# CH32V467WEU-R0.net
KiCad netlist of a schematic drawn in Altium Designer
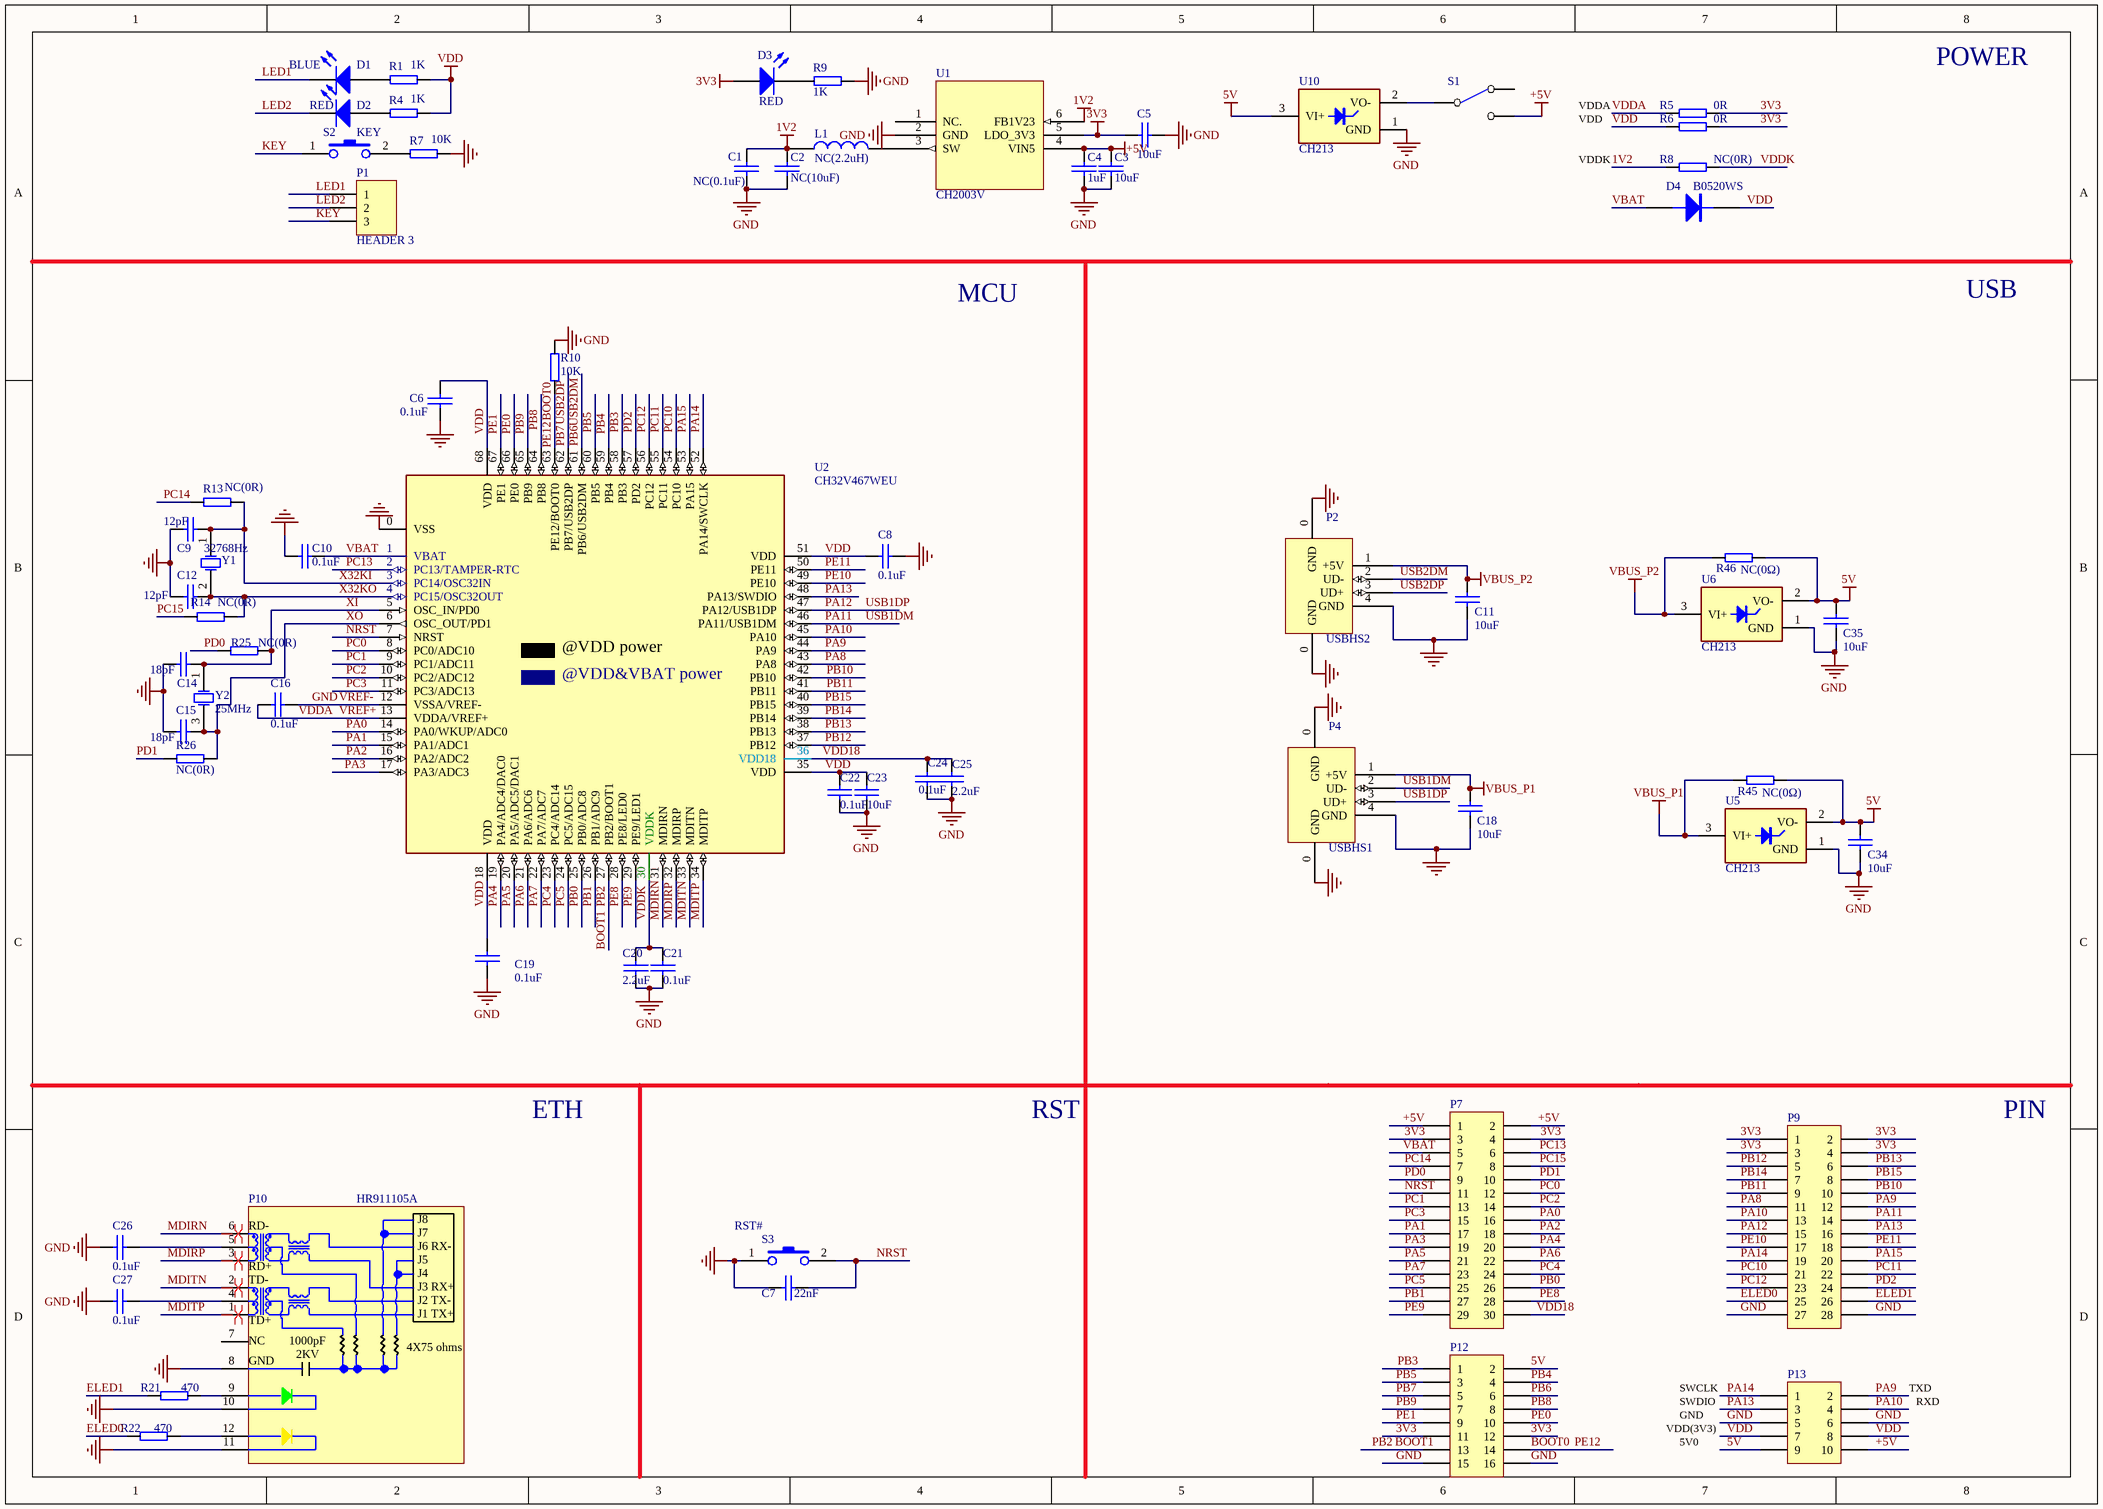
[diagram p0: CH32V467WEU-R0.SchDoc]

(export (version "E")
  (design (tool "Eeschema 10.0.6"))
  (components
    (comp (ref "C1")
      (value "NC(0.1uF)")
      (footprint "0402_C")
      (description "Capacitor")
      (libsource (lib "") (part "CAP_2"))
    )
    (comp (ref "C2")
      (value "NC(10uF)")
      (footprint "0603_C")
      (description "Capacitor")
      (libsource (lib "") (part "CAP_1"))
    )
    (comp (ref "C3")
      (value "10uF")
      (footprint "0603_C")
      (description "Capacitor")
      (libsource (lib "") (part "CAP_1"))
    )
    (comp (ref "C4")
      (value "1uF")
      (footprint "0402_C")
      (description "Capacitor")
      (libsource (lib "") (part "CAP_2"))
    )
    (comp (ref "C5")
      (value "10uF")
      (footprint "0603_C")
      (description "Capacitor")
      (libsource (lib "") (part "CAP_1"))
    )
    (comp (ref "C6")
      (value "0.1uF")
      (footprint "0402_C")
      (description "Capacitor")
      (libsource (lib "") (part "CAP_1"))
    )
    (comp (ref "C7")
      (value "22nF")
      (footprint "0402_C")
      (description "Capacitor")
      (libsource (lib "*") (part "CAP"))
    )
    (comp (ref "C8")
      (value "0.1uF")
      (footprint "0402_C")
      (description "Capacitor")
      (libsource (lib "") (part "CAP_1"))
    )
    (comp (ref "C9")
      (value "12pF")
      (footprint "0402_C")
      (description "Capacitor")
      (libsource (lib "") (part "CAP_1"))
    )
    (comp (ref "C10")
      (value "0.1uF")
      (footprint "0402_C")
      (description "Capacitor")
      (libsource (lib "") (part "CAP_1"))
    )
    (comp (ref "C11")
      (value "10uF")
      (footprint "0603_C")
      (description "Capacitor")
      (libsource (lib "*") (part "CAP"))
    )
    (comp (ref "C12")
      (value "12pF")
      (footprint "0402_C")
      (description "Capacitor")
      (libsource (lib "") (part "CAP_1"))
    )
    (comp (ref "C14")
      (value "18pF")
      (footprint "0402_C")
      (description "Capacitor")
      (libsource (lib "") (part "CAP_1"))
    )
    (comp (ref "C15")
      (value "18pF")
      (footprint "0402_C")
      (description "Capacitor")
      (libsource (lib "") (part "CAP_1"))
    )
    (comp (ref "C16")
      (value "0.1uF")
      (footprint "0402_C")
      (description "Capacitor")
      (libsource (lib "") (part "CAP_1"))
    )
    (comp (ref "C18")
      (value "10uF")
      (footprint "0603_C")
      (description "Capacitor")
      (libsource (lib "*") (part "CAP"))
    )
    (comp (ref "C19")
      (value "0.1uF")
      (footprint "0402_C")
      (description "Capacitor")
      (libsource (lib "") (part "CAP_1"))
    )
    (comp (ref "C20")
      (value "2.2uF")
      (footprint "0402_C")
      (description "Capacitor")
      (libsource (lib "") (part "CAP_1"))
    )
    (comp (ref "C21")
      (value "0.1uF")
      (footprint "0402_C")
      (description "Capacitor")
      (libsource (lib "") (part "CAP_1"))
    )
    (comp (ref "C22")
      (value "0.1uF")
      (footprint "0402_C")
      (description "Capacitor")
      (libsource (lib "") (part "CAP_1"))
    )
    (comp (ref "C23")
      (value "10uF")
      (footprint "0603_C")
      (description "Capacitor")
      (libsource (lib "") (part "CAP_1"))
    )
    (comp (ref "C24")
      (value "0.1uF")
      (footprint "0402_C")
      (description "Capacitor")
      (libsource (lib "") (part "CAP_1"))
    )
    (comp (ref "C25")
      (value "2.2uF")
      (footprint "0402_C")
      (description "Capacitor")
      (libsource (lib "") (part "CAP_1"))
    )
    (comp (ref "C26")
      (value "0.1uF")
      (footprint "0402_C")
      (description "Capacitor")
      (libsource (lib "wch_sch_others") (part "CAP"))
    )
    (comp (ref "C27")
      (value "0.1uF")
      (footprint "0402_C")
      (description "Capacitor")
      (libsource (lib "wch_sch_others") (part "CAP"))
    )
    (comp (ref "C34")
      (value "10uF")
      (footprint "0603_C")
      (description "Capacitor")
      (libsource (lib "*") (part "CAP"))
    )
    (comp (ref "C35")
      (value "10uF")
      (footprint "0603_C")
      (description "Capacitor")
      (libsource (lib "*") (part "CAP"))
    )
    (comp (ref "D1")
      (value "BLUE")
      (footprint "0603+")
      (description "Typical INFRARED GaAs LED")
      (fields (field (name "PUBLISHER") "Altium Limited"))
      (libsource (lib "*") (part "LED0"))
    )
    (comp (ref "D2")
      (value "RED")
      (footprint "0603+")
      (description "Typical INFRARED GaAs LED")
      (fields (field (name "PUBLISHER") "Altium Limited"))
      (libsource (lib "*") (part "LED0"))
    )
    (comp (ref "D3")
      (value "RED")
      (footprint "0603+")
      (description "Typical INFRARED GaAs LED")
      (fields (field (name "PUBLISHER") "Altium Limited"))
      (libsource (lib "*") (part "LED0"))
    )
    (comp (ref "D4")
      (value "B0520WS")
      (footprint "SOD-323")
      (description "Diode")
      (libsource (lib "*") (part "DIODE"))
    )
    (comp (ref "L1") (value "NC(2.2uH)") (footprint "CD32") (libsource (lib "*") (part "INDUCTOR")))
    (comp (ref "P1")
      (value "HEADER 3")
      (footprint "SIP3-2.54MM")
      (description "Header, 3-Pin")
      (libsource (lib "wch_sch_others") (part "HEADER 3"))
    )
    (comp (ref "P2")
      (value "USBHS2")
      (footprint "USBAF")
      (description "USB Port")
      (libsource (lib "*") (part "USB"))
    )
    (comp (ref "P4")
      (value "USBHS1")
      (footprint "USBAF")
      (description "USB Port")
      (libsource (lib "*") (part "USB"))
    )
    (comp (ref "P7")
      (value "HEADER 15x2")
      (footprint "MYPCB:IDC30-2.54MM")
      (description "Header, 15-Pin, Dual row")
      (libsource (lib "wch_sch_others") (part "HEADER 15x2"))
    )
    (comp (ref "P9")
      (value "HEADER 14x2")
      (footprint "MYPCB:IDC28-2.54MM")
      (description "Header, 14-Pin, Dual row")
      (libsource (lib "wch_sch_others") (part "HEADER 14x2"))
    )
    (comp (ref "P10") (value "HR911105A") (footprint "HR911105A") (libsource (lib "*") (part "HR911105A")))
    (comp (ref "P12")
      (value "Ppin")
      (footprint "IDC16-2.54mm")
      (description "Header, 8-Pin, Dual row, Right Angle")
      (fields (field (name "PUBLISHER") "Altium Limited"))
      (libsource (lib "Miscellaneous Connectors") (part "Header 8X2H"))
    )
    (comp (ref "P13")
      (value "LINK")
      (footprint "IDC10-2.54mm")
      (description "Header, 5-Pin, Dual row, Right Angle")
      (fields (field (name "PUBLISHER") "Altium Limited"))
      (libsource (lib "Miscellaneous Connectors") (part "Header 5X2H"))
    )
    (comp (ref "R1") (value "1K") (footprint "0402") (libsource (lib "wch_sch_others") (part "RES")))
    (comp (ref "R4") (value "1K") (footprint "0402") (libsource (lib "wch_sch_others") (part "RES")))
    (comp (ref "R5") (value "0R") (footprint "0402") (libsource (lib "*") (part "R")))
    (comp (ref "R6") (value "0R") (footprint "0402") (libsource (lib "*") (part "R")))
    (comp (ref "R7") (value "10K") (footprint "0402") (libsource (lib "wch_sch_others") (part "RES")))
    (comp (ref "R8") (value "NC(0R)") (footprint "0402") (libsource (lib "*") (part "R")))
    (comp (ref "R9") (value "1K") (footprint "0402") (libsource (lib "wch_sch_others") (part "RES")))
    (comp (ref "R10") (value "10K") (footprint "0402") (libsource (lib "wch_sch_others") (part "RES")))
    (comp (ref "R13") (value "NC(0R)") (footprint "0402") (libsource (lib "wch_sch_others") (part "RES")))
    (comp (ref "R14") (value "NC(0R)") (footprint "0402") (libsource (lib "wch_sch_others") (part "RES")))
    (comp (ref "R21") (value "470") (footprint "0402") (libsource (lib "wch_sch_others") (part "RES")))
    (comp (ref "R22") (value "470") (footprint "0402") (libsource (lib "wch_sch_others") (part "RES")))
    (comp (ref "R25") (value "NC(0R)") (footprint "0402") (libsource (lib "wch_sch_others") (part "RES")))
    (comp (ref "R26") (value "NC(0R)") (footprint "0402") (libsource (lib "wch_sch_others") (part "RES")))
    (comp (ref "R45") (value "NC(0Ω)") (footprint "0402") (libsource (lib "wch_sch_others") (part "RES")))
    (comp (ref "R46") (value "NC(0Ω)") (footprint "0402") (libsource (lib "wch_sch_others") (part "RES")))
    (comp (ref "S1") (value "SW SPDT") (footprint "SW1") (libsource (lib "*") (part "SW SPDT")))
    (comp (ref "S2")
      (value "KEY")
      (footprint "SMD_6.1x3.65x2.5mm-KEY")
      (libsource (lib "wch_sch_others") (part "KEY1"))
    )
    (comp (ref "S3")
      (value "RST#")
      (footprint "SMD_6.1x3.65x2.5mm-KEY")
      (libsource (lib "wch_sch_others") (part "KEY1"))
    )
    (comp (ref "U1")
      (value "CH2003V")
      (footprint "SOT-23-6")
      (description "Step-Down DC-DC Converter, 5V input, 1.23V * 800mA output, with LDO 3.3V * 200mA")
      (libsource (lib "CHXXX") (part "CH2003V"))
    )
    (comp (ref "U2")
      (value "CH32V467WEU")
      (footprint "QFN68_8X8")
      (description "RISC-V FPU HD-MCU, 175MHz, USB_480M, 100M Ethernet & Phy, CAN, ADC, DAC, SRAM")
      (libsource (lib "CHXXX") (part "CH32V467WEU"))
    )
    (comp (ref "U5")
      (value "CH213")
      (footprint "SOT-23-3")
      (description "Ideal Diode 5V*1A")
      (libsource (lib "CHXXX") (part "CH213E"))
    )
    (comp (ref "U6")
      (value "CH213")
      (footprint "SOT-23-3")
      (description "Ideal Diode 5V*1A")
      (libsource (lib "CHXXX") (part "CH213E"))
    )
    (comp (ref "U10")
      (value "CH213")
      (footprint "SOT-23-3")
      (description "Ideal Diode 5V*1A")
      (libsource (lib "CHXXX") (part "CH213E"))
    )
    (comp (ref "Y1")
      (value "32768Hz")
      (footprint "FC-135")
      (description "Crystal Oscillator")
      (fields (field (name "PUBLISHER") "Altium Limited"))
      (libsource (lib "*") (part "XTAL"))
    )
    (comp (ref "Y2")
      (value "25MHz")
      (footprint "XT3225")
      (description "Crystal Oscillator")
      (fields (field (name "PUBLISHER") "Altium Limited"))
      (libsource (lib "") (part "XTAL_1"))
    )
  )
  (nets
    (net (code "1") (name "+5V") (class "Default")
      (node (ref "C3") (pin "2") (pinfunction "2_2") (pintype "passive"))
      (node (ref "C4") (pin "2") (pinfunction "2_2") (pintype "passive"))
      (node (ref "P13") (pin "10") (pinfunction "10_10") (pintype "passive"))
      (node (ref "P7") (pin "1") (pinfunction "1_1") (pintype "passive"))
      (node (ref "P7") (pin "2") (pinfunction "2_2") (pintype "passive"))
      (node (ref "S1") (pin "2") (pinfunction "NC_2") (pintype "passive"))
      (node (ref "U1") (pin "4") (pinfunction "VIN5_4") (pintype "power_in"))
    )
    (net (code "3") (name "/BOOT0") (class "Default")
      (node (ref "P12") (pin "14") (pinfunction "14_14") (pintype "passive"))
      (node (ref "R10") (pin "2") (pintype "passive"))
      (node (ref "U2") (pin "63") (pinfunction "PE12/BOOT0_63") (pintype "bidirectional"))
    )
    (net (code "4") (name "/BOOT1") (class "Default")
      (node (ref "P12") (pin "13") (pinfunction "13_13") (pintype "passive"))
      (node (ref "U2") (pin "27") (pinfunction "PB2/BOOT1_27") (pintype "bidirectional"))
    )
    (net (code "5") (name "/ELED0") (class "Default")
      (node (ref "P9") (pin "25") (pinfunction "25_25") (pintype "passive"))
      (node (ref "R22") (pin "1") (pintype "passive"))
    )
    (net (code "6") (name "/ELED1") (class "Default")
      (node (ref "P9") (pin "26") (pinfunction "26_26") (pintype "passive"))
      (node (ref "R21") (pin "1") (pintype "passive"))
    )
    (net (code "7") (name "/KEY") (class "Default")
      (node (ref "P1") (pin "3") (pinfunction "3_3") (pintype "passive"))
      (node (ref "S2") (pin "1") (pinfunction "1_1") (pintype "passive"))
    )
    (net (code "8") (name "/LED1") (class "Default")
      (node (ref "D1") (pin "2") (pinfunction "K_2") (pintype "passive"))
      (node (ref "P1") (pin "1") (pinfunction "1_1") (pintype "passive"))
    )
    (net (code "9") (name "/LED2") (class "Default")
      (node (ref "D2") (pin "2") (pinfunction "K_2") (pintype "passive"))
      (node (ref "P1") (pin "2") (pinfunction "2_2") (pintype "passive"))
    )
    (net (code "10") (name "/MDIRN") (class "Default")
      (node (ref "P10") (pin "6") (pintype "passive"))
      (node (ref "U2") (pin "31") (pinfunction "MDIRN_31") (pintype "bidirectional"))
    )
    (net (code "11") (name "/MDIRP") (class "Default")
      (node (ref "P10") (pin "3") (pintype "passive"))
      (node (ref "U2") (pin "32") (pinfunction "MDIRP_32") (pintype "bidirectional"))
    )
    (net (code "12") (name "/MDITN") (class "Default")
      (node (ref "P10") (pin "2") (pintype "passive"))
      (node (ref "U2") (pin "33") (pinfunction "MDITN_33") (pintype "bidirectional"))
    )
    (net (code "13") (name "/MDITP") (class "Default")
      (node (ref "P10") (pin "1") (pintype "passive"))
      (node (ref "U2") (pin "34") (pinfunction "MDITP_34") (pintype "bidirectional"))
    )
    (net (code "14") (name "/NRST") (class "Default")
      (node (ref "C7") (pin "2") (pinfunction "2_2") (pintype "passive"))
      (node (ref "P7") (pin "11") (pinfunction "11_11") (pintype "passive"))
      (node (ref "S3") (pin "2") (pinfunction "2_2") (pintype "passive"))
      (node (ref "U2") (pin "7") (pinfunction "NRST_7") (pintype "input"))
    )
    (net (code "15") (name "/PA0") (class "Default")
      (node (ref "P7") (pin "16") (pinfunction "16_16") (pintype "passive"))
      (node (ref "U2") (pin "14") (pinfunction "PA0/WKUP/ADC0_14") (pintype "bidirectional"))
    )
    (net (code "16") (name "/PA1") (class "Default")
      (node (ref "P7") (pin "17") (pinfunction "17_17") (pintype "passive"))
      (node (ref "U2") (pin "15") (pinfunction "PA1/ADC1_15") (pintype "bidirectional"))
    )
    (net (code "17") (name "/PA2") (class "Default")
      (node (ref "P7") (pin "18") (pinfunction "18_18") (pintype "passive"))
      (node (ref "U2") (pin "16") (pinfunction "PA2/ADC2_16") (pintype "bidirectional"))
    )
    (net (code "18") (name "/PA3") (class "Default")
      (node (ref "P7") (pin "19") (pinfunction "19_19") (pintype "passive"))
      (node (ref "U2") (pin "17") (pinfunction "PA3/ADC3_17") (pintype "bidirectional"))
    )
    (net (code "19") (name "/PA4") (class "Default")
      (node (ref "P7") (pin "20") (pinfunction "20_20") (pintype "passive"))
      (node (ref "U2") (pin "19") (pinfunction "PA4/ADC4/DAC0_19") (pintype "bidirectional"))
    )
    (net (code "20") (name "/PA5") (class "Default")
      (node (ref "P7") (pin "21") (pinfunction "21_21") (pintype "passive"))
      (node (ref "U2") (pin "20") (pinfunction "PA5/ADC5/DAC1_20") (pintype "bidirectional"))
    )
    (net (code "21") (name "/PA6") (class "Default")
      (node (ref "P7") (pin "22") (pinfunction "22_22") (pintype "passive"))
      (node (ref "U2") (pin "21") (pinfunction "PA6/ADC6_21") (pintype "bidirectional"))
    )
    (net (code "22") (name "/PA7") (class "Default")
      (node (ref "P7") (pin "23") (pinfunction "23_23") (pintype "passive"))
      (node (ref "U2") (pin "22") (pinfunction "PA7/ADC7_22") (pintype "bidirectional"))
    )
    (net (code "23") (name "/PA8") (class "Default")
      (node (ref "P9") (pin "11") (pinfunction "11_11") (pintype "passive"))
      (node (ref "U2") (pin "43") (pinfunction "PA8_43") (pintype "bidirectional"))
    )
    (net (code "24") (name "/PA9") (class "Default")
      (node (ref "P13") (pin "2") (pinfunction "2_2") (pintype "passive"))
      (node (ref "P9") (pin "12") (pinfunction "12_12") (pintype "passive"))
      (node (ref "U2") (pin "44") (pinfunction "PA9_44") (pintype "bidirectional"))
    )
    (net (code "25") (name "/PA10") (class "Default")
      (node (ref "P13") (pin "4") (pinfunction "4_4") (pintype "passive"))
      (node (ref "P9") (pin "13") (pinfunction "13_13") (pintype "passive"))
      (node (ref "U2") (pin "45") (pinfunction "PA10_45") (pintype "bidirectional"))
    )
    (net (code "26") (name "/PA11") (class "Default")
      (node (ref "P4") (pin "2") (pinfunction "UD-_2") (pintype "bidirectional"))
      (node (ref "P9") (pin "14") (pinfunction "14_14") (pintype "passive"))
      (node (ref "U2") (pin "46") (pinfunction "PA11/USB1DM_46") (pintype "bidirectional"))
    )
    (net (code "27") (name "/PA12") (class "Default")
      (node (ref "P4") (pin "3") (pinfunction "UD+_3") (pintype "bidirectional"))
      (node (ref "P9") (pin "15") (pinfunction "15_15") (pintype "passive"))
      (node (ref "U2") (pin "47") (pinfunction "PA12/USB1DP_47") (pintype "bidirectional"))
    )
    (net (code "28") (name "/PA13") (class "Default")
      (node (ref "P13") (pin "3") (pinfunction "3_3") (pintype "passive"))
      (node (ref "P9") (pin "16") (pinfunction "16_16") (pintype "passive"))
      (node (ref "U2") (pin "48") (pinfunction "PA13/SWDIO_48") (pintype "bidirectional"))
    )
    (net (code "29") (name "/PA14") (class "Default")
      (node (ref "P13") (pin "1") (pinfunction "1_1") (pintype "passive"))
      (node (ref "P9") (pin "19") (pinfunction "19_19") (pintype "passive"))
      (node (ref "U2") (pin "52") (pinfunction "PA14/SWCLK_52") (pintype "bidirectional"))
    )
    (net (code "30") (name "/PA15") (class "Default")
      (node (ref "P9") (pin "20") (pinfunction "20_20") (pintype "passive"))
      (node (ref "U2") (pin "53") (pinfunction "PA15_53") (pintype "bidirectional"))
    )
    (net (code "31") (name "/PB0") (class "Default")
      (node (ref "P7") (pin "26") (pinfunction "26_26") (pintype "passive"))
      (node (ref "U2") (pin "25") (pinfunction "PB0/ADC8_25") (pintype "bidirectional"))
    )
    (net (code "32") (name "/PB1") (class "Default")
      (node (ref "P7") (pin "27") (pinfunction "27_27") (pintype "passive"))
      (node (ref "U2") (pin "26") (pinfunction "PB1/ADC9_26") (pintype "bidirectional"))
    )
    (net (code "33") (name "/PB3") (class "Default")
      (node (ref "P12") (pin "1") (pinfunction "1_1") (pintype "passive"))
      (node (ref "U2") (pin "58") (pinfunction "PB3_58") (pintype "bidirectional"))
    )
    (net (code "34") (name "/PB4") (class "Default")
      (node (ref "P12") (pin "4") (pinfunction "4_4") (pintype "passive"))
      (node (ref "U2") (pin "59") (pinfunction "PB4_59") (pintype "bidirectional"))
    )
    (net (code "35") (name "/PB5") (class "Default")
      (node (ref "P12") (pin "3") (pinfunction "3_3") (pintype "passive"))
      (node (ref "U2") (pin "60") (pinfunction "PB5_60") (pintype "bidirectional"))
    )
    (net (code "36") (name "/PB6") (class "Default")
      (node (ref "P12") (pin "6") (pinfunction "6_6") (pintype "passive"))
      (node (ref "P2") (pin "2") (pinfunction "UD-_2") (pintype "bidirectional"))
      (node (ref "U2") (pin "61") (pinfunction "PB6/USB2DM_61") (pintype "bidirectional"))
    )
    (net (code "37") (name "/PB7") (class "Default")
      (node (ref "P12") (pin "5") (pinfunction "5_5") (pintype "passive"))
      (node (ref "P2") (pin "3") (pinfunction "UD+_3") (pintype "bidirectional"))
      (node (ref "U2") (pin "62") (pinfunction "PB7/USB2DP_62") (pintype "bidirectional"))
    )
    (net (code "38") (name "/PB8") (class "Default")
      (node (ref "P12") (pin "8") (pinfunction "8_8") (pintype "passive"))
      (node (ref "U2") (pin "64") (pinfunction "PB8_64") (pintype "bidirectional"))
    )
    (net (code "39") (name "/PB9") (class "Default")
      (node (ref "P12") (pin "7") (pinfunction "7_7") (pintype "passive"))
      (node (ref "U2") (pin "65") (pinfunction "PB9_65") (pintype "bidirectional"))
    )
    (net (code "40") (name "/PB10") (class "Default")
      (node (ref "P9") (pin "10") (pinfunction "10_10") (pintype "passive"))
      (node (ref "U2") (pin "42") (pinfunction "PB10_42") (pintype "bidirectional"))
    )
    (net (code "41") (name "/PB11") (class "Default")
      (node (ref "P9") (pin "9") (pinfunction "9_9") (pintype "passive"))
      (node (ref "U2") (pin "41") (pinfunction "PB11_41") (pintype "bidirectional"))
    )
    (net (code "42") (name "/PB12") (class "Default")
      (node (ref "P9") (pin "5") (pinfunction "5_5") (pintype "passive"))
      (node (ref "U2") (pin "37") (pinfunction "PB12_37") (pintype "bidirectional"))
    )
    (net (code "43") (name "/PB13") (class "Default")
      (node (ref "P9") (pin "6") (pinfunction "6_6") (pintype "passive"))
      (node (ref "U2") (pin "38") (pinfunction "PB13_38") (pintype "bidirectional"))
    )
    (net (code "44") (name "/PB14") (class "Default")
      (node (ref "P9") (pin "7") (pinfunction "7_7") (pintype "passive"))
      (node (ref "U2") (pin "39") (pinfunction "PB14_39") (pintype "bidirectional"))
    )
    (net (code "45") (name "/PB15") (class "Default")
      (node (ref "P9") (pin "8") (pinfunction "8_8") (pintype "passive"))
      (node (ref "U2") (pin "40") (pinfunction "PB15_40") (pintype "bidirectional"))
    )
    (net (code "46") (name "/PC0") (class "Default")
      (node (ref "P7") (pin "12") (pinfunction "12_12") (pintype "passive"))
      (node (ref "U2") (pin "8") (pinfunction "PC0/ADC10_8") (pintype "bidirectional"))
    )
    (net (code "47") (name "/PC1") (class "Default")
      (node (ref "P7") (pin "13") (pinfunction "13_13") (pintype "passive"))
      (node (ref "U2") (pin "9") (pinfunction "PC1/ADC11_9") (pintype "bidirectional"))
    )
    (net (code "48") (name "/PC2") (class "Default")
      (node (ref "P7") (pin "14") (pinfunction "14_14") (pintype "passive"))
      (node (ref "U2") (pin "10") (pinfunction "PC2/ADC12_10") (pintype "bidirectional"))
    )
    (net (code "49") (name "/PC3") (class "Default")
      (node (ref "P7") (pin "15") (pinfunction "15_15") (pintype "passive"))
      (node (ref "U2") (pin "11") (pinfunction "PC3/ADC13_11") (pintype "bidirectional"))
    )
    (net (code "50") (name "/PC4") (class "Default")
      (node (ref "P7") (pin "24") (pinfunction "24_24") (pintype "passive"))
      (node (ref "U2") (pin "23") (pinfunction "PC4/ADC14_23") (pintype "bidirectional"))
    )
    (net (code "51") (name "/PC5") (class "Default")
      (node (ref "P7") (pin "25") (pinfunction "25_25") (pintype "passive"))
      (node (ref "U2") (pin "24") (pinfunction "PC5/ADC15_24") (pintype "bidirectional"))
    )
    (net (code "52") (name "/PC10") (class "Default")
      (node (ref "P9") (pin "21") (pinfunction "21_21") (pintype "passive"))
      (node (ref "U2") (pin "54") (pinfunction "PC10_54") (pintype "bidirectional"))
    )
    (net (code "53") (name "/PC11") (class "Default")
      (node (ref "P9") (pin "22") (pinfunction "22_22") (pintype "passive"))
      (node (ref "U2") (pin "55") (pinfunction "PC11_55") (pintype "bidirectional"))
    )
    (net (code "54") (name "/PC12") (class "Default")
      (node (ref "P9") (pin "23") (pinfunction "23_23") (pintype "passive"))
      (node (ref "U2") (pin "56") (pinfunction "PC12_56") (pintype "bidirectional"))
    )
    (net (code "55") (name "/PC13") (class "Default")
      (node (ref "P7") (pin "6") (pinfunction "6_6") (pintype "passive"))
      (node (ref "U2") (pin "2") (pinfunction "PC13/TAMPER-RTC_2") (pintype "bidirectional"))
    )
    (net (code "56") (name "/PC14") (class "Default")
      (node (ref "P7") (pin "7") (pinfunction "7_7") (pintype "passive"))
      (node (ref "R13") (pin "1") (pintype "passive"))
    )
    (net (code "57") (name "/PC15") (class "Default")
      (node (ref "P7") (pin "8") (pinfunction "8_8") (pintype "passive"))
      (node (ref "R14") (pin "1") (pintype "passive"))
    )
    (net (code "58") (name "/PD0") (class "Default")
      (node (ref "P7") (pin "9") (pinfunction "9_9") (pintype "passive"))
      (node (ref "R25") (pin "1") (pintype "passive"))
    )
    (net (code "59") (name "/PD1") (class "Default")
      (node (ref "P7") (pin "10") (pinfunction "10_10") (pintype "passive"))
      (node (ref "R26") (pin "2") (pintype "passive"))
    )
    (net (code "60") (name "/PD2") (class "Default")
      (node (ref "P9") (pin "24") (pinfunction "24_24") (pintype "passive"))
      (node (ref "U2") (pin "57") (pinfunction "PD2_57") (pintype "bidirectional"))
    )
    (net (code "61") (name "/PE0") (class "Default")
      (node (ref "P12") (pin "10") (pinfunction "10_10") (pintype "passive"))
      (node (ref "U2") (pin "66") (pinfunction "PE0_66") (pintype "bidirectional"))
    )
    (net (code "62") (name "/PE1") (class "Default")
      (node (ref "P12") (pin "9") (pinfunction "9_9") (pintype "passive"))
      (node (ref "U2") (pin "67") (pinfunction "PE1_67") (pintype "bidirectional"))
    )
    (net (code "63") (name "/PE8") (class "Default")
      (node (ref "P7") (pin "28") (pinfunction "28_28") (pintype "passive"))
      (node (ref "U2") (pin "28") (pinfunction "PE8/LED0_28") (pintype "bidirectional"))
    )
    (net (code "64") (name "/PE9") (class "Default")
      (node (ref "P7") (pin "29") (pinfunction "29_29") (pintype "passive"))
      (node (ref "U2") (pin "29") (pinfunction "PE9/LED1_29") (pintype "bidirectional"))
    )
    (net (code "65") (name "/PE10") (class "Default")
      (node (ref "P9") (pin "17") (pinfunction "17_17") (pintype "passive"))
      (node (ref "U2") (pin "49") (pinfunction "PE10_49") (pintype "bidirectional"))
    )
    (net (code "66") (name "/PE11") (class "Default")
      (node (ref "P9") (pin "18") (pinfunction "18_18") (pintype "passive"))
      (node (ref "U2") (pin "50") (pinfunction "PE11_50") (pintype "bidirectional"))
    )
    (net (code "67") (name "/VBAT") (class "Default")
      (node (ref "C10") (pin "2") (pinfunction "2_2") (pintype "passive"))
      (node (ref "D4") (pin "1") (pinfunction "A_1") (pintype "passive"))
      (node (ref "P7") (pin "5") (pinfunction "5_5") (pintype "passive"))
      (node (ref "U2") (pin "1") (pinfunction "VBAT_1") (pintype "power_in"))
    )
    (net (code "68") (name "/VDD18") (class "Default")
      (node (ref "C24") (pin "2") (pinfunction "2_2") (pintype "passive"))
      (node (ref "C25") (pin "2") (pinfunction "2_2") (pintype "passive"))
      (node (ref "P7") (pin "30") (pinfunction "30_30") (pintype "passive"))
      (node (ref "U2") (pin "36") (pinfunction "VDD18_36") (pintype "power_in"))
    )
    (net (code "69") (name "/VDDA") (class "Default")
      (node (ref "C16") (pin "1") (pinfunction "1_1") (pintype "passive"))
      (node (ref "R5") (pin "2") (pinfunction "2_2") (pintype "passive"))
      (node (ref "U2") (pin "13") (pinfunction "VDDA/VREF+_13") (pintype "power_in"))
    )
    (net (code "70") (name "/VDDK") (class "Default")
      (node (ref "C20") (pin "2") (pinfunction "2_2") (pintype "passive"))
      (node (ref "C21") (pin "2") (pinfunction "2_2") (pintype "passive"))
      (node (ref "R8") (pin "1") (pinfunction "1_1") (pintype "passive"))
      (node (ref "U2") (pin "30") (pinfunction "VDDK_30") (pintype "power_in"))
    )
    (net (code "71") (name "/X32KI") (class "Default")
      (node (ref "C9") (pin "2") (pinfunction "2_2") (pintype "passive"))
      (node (ref "R13") (pin "2") (pintype "passive"))
      (node (ref "U2") (pin "3") (pinfunction "PC14/OSC32IN_3") (pintype "bidirectional"))
      (node (ref "Y1") (pin "1") (pinfunction "OSC1_1") (pintype "passive"))
    )
    (net (code "72") (name "/X32KO") (class "Default")
      (node (ref "C12") (pin "2") (pinfunction "2_2") (pintype "passive"))
      (node (ref "R14") (pin "2") (pintype "passive"))
      (node (ref "U2") (pin "4") (pinfunction "PC15/OSC32OUT_4") (pintype "bidirectional"))
      (node (ref "Y1") (pin "2") (pinfunction "OSC2_2") (pintype "passive"))
    )
    (net (code "73") (name "/XI") (class "Default")
      (node (ref "C14") (pin "2") (pinfunction "2_2") (pintype "passive"))
      (node (ref "R25") (pin "2") (pintype "passive"))
      (node (ref "U2") (pin "5") (pinfunction "OSC_IN/PD0_5") (pintype "input"))
      (node (ref "Y2") (pin "1") (pinfunction "OSC1_1") (pintype "passive"))
    )
    (net (code "74") (name "/XO") (class "Default")
      (node (ref "C15") (pin "2") (pinfunction "2_2") (pintype "passive"))
      (node (ref "R26") (pin "1") (pintype "passive"))
      (node (ref "U2") (pin "6") (pinfunction "OSC_OUT/PD1_6") (pintype "output"))
      (node (ref "Y2") (pin "3") (pinfunction "OSC2_3") (pintype "passive"))
    )
    (net (code "75") (name "1V2") (class "Default")
      (node (ref "C1") (pin "2") (pinfunction "2_2") (pintype "passive"))
      (node (ref "C2") (pin "2") (pinfunction "2_2") (pintype "passive"))
      (node (ref "L1") (pin "2") (pinfunction "2_2") (pintype "passive"))
      (node (ref "R8") (pin "2") (pinfunction "2_2") (pintype "passive"))
      (node (ref "U1") (pin "6") (pinfunction "FB1V23_6") (pintype "input"))
    )
    (net (code "76") (name "3V3") (class "Default")
      (node (ref "C5") (pin "2") (pinfunction "2_2") (pintype "passive"))
      (node (ref "D3") (pin "1") (pinfunction "A_1") (pintype "passive"))
      (node (ref "P12") (pin "11") (pinfunction "11_11") (pintype "passive"))
      (node (ref "P12") (pin "12") (pinfunction "12_12") (pintype "passive"))
      (node (ref "P7") (pin "3") (pinfunction "3_3") (pintype "passive"))
      (node (ref "P7") (pin "4") (pinfunction "4_4") (pintype "passive"))
      (node (ref "P9") (pin "1") (pinfunction "1_1") (pintype "passive"))
      (node (ref "P9") (pin "2") (pinfunction "2_2") (pintype "passive"))
      (node (ref "P9") (pin "3") (pinfunction "3_3") (pintype "passive"))
      (node (ref "P9") (pin "4") (pinfunction "4_4") (pintype "passive"))
      (node (ref "R5") (pin "1") (pinfunction "1_1") (pintype "passive"))
      (node (ref "R6") (pin "1") (pinfunction "1_1") (pintype "passive"))
      (node (ref "U1") (pin "5") (pinfunction "LDO_3V3_5") (pintype "power_in"))
    )
    (net (code "77") (name "5V") (class "Default")
      (node (ref "C34") (pin "1") (pinfunction "1_1") (pintype "passive"))
      (node (ref "C35") (pin "1") (pinfunction "1_1") (pintype "passive"))
      (node (ref "P12") (pin "2") (pinfunction "2_2") (pintype "passive"))
      (node (ref "P13") (pin "9") (pinfunction "9_9") (pintype "passive"))
      (node (ref "R45") (pin "1") (pintype "passive"))
      (node (ref "R46") (pin "1") (pintype "passive"))
      (node (ref "U10") (pin "3") (pinfunction "VI+_3") (pintype "power_in"))
      (node (ref "U5") (pin "2") (pinfunction "VO-_2") (pintype "power_in"))
      (node (ref "U6") (pin "2") (pinfunction "VO-_2") (pintype "power_in"))
    )
    (net (code "78") (name "GND") (class "Default")
      (node (ref "C1") (pin "1") (pinfunction "1_1") (pintype "passive"))
      (node (ref "C10") (pin "1") (pinfunction "1_1") (pintype "passive"))
      (node (ref "C11") (pin "2") (pinfunction "2_2") (pintype "passive"))
      (node (ref "C12") (pin "1") (pinfunction "1_1") (pintype "passive"))
      (node (ref "C14") (pin "1") (pinfunction "1_1") (pintype "passive"))
      (node (ref "C15") (pin "1") (pinfunction "1_1") (pintype "passive"))
      (node (ref "C16") (pin "2") (pinfunction "2_2") (pintype "passive"))
      (node (ref "C18") (pin "2") (pinfunction "2_2") (pintype "passive"))
      (node (ref "C19") (pin "1") (pinfunction "1_1") (pintype "passive"))
      (node (ref "C2") (pin "1") (pinfunction "1_1") (pintype "passive"))
      (node (ref "C20") (pin "1") (pinfunction "1_1") (pintype "passive"))
      (node (ref "C21") (pin "1") (pinfunction "1_1") (pintype "passive"))
      (node (ref "C22") (pin "1") (pinfunction "1_1") (pintype "passive"))
      (node (ref "C23") (pin "1") (pinfunction "1_1") (pintype "passive"))
      (node (ref "C24") (pin "1") (pinfunction "1_1") (pintype "passive"))
      (node (ref "C25") (pin "1") (pinfunction "1_1") (pintype "passive"))
      (node (ref "C26") (pin "1") (pinfunction "1_1") (pintype "passive"))
      (node (ref "C27") (pin "1") (pinfunction "1_1") (pintype "passive"))
      (node (ref "C3") (pin "1") (pinfunction "1_1") (pintype "passive"))
      (node (ref "C34") (pin "2") (pinfunction "2_2") (pintype "passive"))
      (node (ref "C35") (pin "2") (pinfunction "2_2") (pintype "passive"))
      (node (ref "C4") (pin "1") (pinfunction "1_1") (pintype "passive"))
      (node (ref "C5") (pin "1") (pinfunction "1_1") (pintype "passive"))
      (node (ref "C6") (pin "1") (pinfunction "1_1") (pintype "passive"))
      (node (ref "C7") (pin "1") (pinfunction "1_1") (pintype "passive"))
      (node (ref "C8") (pin "2") (pinfunction "2_2") (pintype "passive"))
      (node (ref "C9") (pin "1") (pinfunction "1_1") (pintype "passive"))
      (node (ref "P10") (pin "10") (pintype "passive"))
      (node (ref "P10") (pin "11") (pintype "passive"))
      (node (ref "P10") (pin "8") (pintype "passive"))
      (node (ref "P12") (pin "15") (pinfunction "15_15") (pintype "passive"))
      (node (ref "P12") (pin "16") (pinfunction "16_16") (pintype "passive"))
      (node (ref "P13") (pin "5") (pinfunction "5_5") (pintype "passive"))
      (node (ref "P13") (pin "6") (pinfunction "6_6") (pintype "passive"))
      (node (ref "P2") (pin "0") (pinfunction "GND_0") (pintype "power_in"))
      (node (ref "P2") (pin "4") (pinfunction "GND_4") (pintype "power_in"))
      (node (ref "P4") (pin "0") (pinfunction "GND_0") (pintype "power_in"))
      (node (ref "P4") (pin "4") (pinfunction "GND_4") (pintype "power_in"))
      (node (ref "P9") (pin "27") (pinfunction "27_27") (pintype "passive"))
      (node (ref "P9") (pin "28") (pinfunction "28_28") (pintype "passive"))
      (node (ref "R10") (pin "1") (pintype "passive"))
      (node (ref "R7") (pin "1") (pintype "passive"))
      (node (ref "R9") (pin "2") (pintype "passive"))
      (node (ref "S3") (pin "1") (pinfunction "1_1") (pintype "passive"))
      (node (ref "U1") (pin "2") (pinfunction "GND_2") (pintype "power_in"))
      (node (ref "U10") (pin "1") (pinfunction "GND_1") (pintype "power_in"))
      (node (ref "U2") (pin "0") (pinfunction "VSS_0") (pintype "power_in"))
      (node (ref "U2") (pin "12") (pinfunction "VSSA/VREF-_12") (pintype "power_in"))
      (node (ref "U5") (pin "1") (pinfunction "GND_1") (pintype "power_in"))
      (node (ref "U6") (pin "1") (pinfunction "GND_1") (pintype "power_in"))
    )
    (net (code "79") (name "Net-(C26-Pad2)") (class "Default")
      (node (ref "C26") (pin "2") (pinfunction "2_2") (pintype "passive"))
      (node (ref "P10") (pin "5") (pintype "passive"))
    )
    (net (code "80") (name "Net-(C27-Pad2)") (class "Default")
      (node (ref "C27") (pin "2") (pinfunction "2_2") (pintype "passive"))
      (node (ref "P10") (pin "4") (pintype "passive"))
    )
    (net (code "81") (name "Net-(D1-A)") (class "Default")
      (node (ref "D1") (pin "1") (pinfunction "A_1") (pintype "passive"))
      (node (ref "R1") (pin "2") (pintype "passive"))
    )
    (net (code "82") (name "Net-(D2-A)") (class "Default")
      (node (ref "D2") (pin "1") (pinfunction "A_1") (pintype "passive"))
      (node (ref "R4") (pin "2") (pintype "passive"))
    )
    (net (code "83") (name "Net-(D3-K)") (class "Default")
      (node (ref "D3") (pin "2") (pinfunction "K_2") (pintype "passive"))
      (node (ref "R9") (pin "1") (pintype "passive"))
    )
    (net (code "84") (name "Net-(P10-Pad9)") (class "Default")
      (node (ref "P10") (pin "9") (pintype "passive"))
      (node (ref "R21") (pin "2") (pintype "passive"))
    )
    (net (code "85") (name "Net-(P10-Pad12)") (class "Default")
      (node (ref "P10") (pin "12") (pintype "passive"))
      (node (ref "R22") (pin "2") (pintype "passive"))
    )
    (net (code "86") (name "Net-(R7-Pad2)") (class "Default")
      (node (ref "R7") (pin "2") (pintype "passive"))
      (node (ref "S2") (pin "2") (pinfunction "2_2") (pintype "passive"))
    )
    (net (code "87") (name "Net-(S1-COMMON)") (class "Default")
      (node (ref "S1") (pin "1") (pinfunction "COMMON_1") (pintype "passive"))
      (node (ref "U10") (pin "2") (pinfunction "VO-_2") (pintype "power_in"))
    )
    (net (code "88") (name "Net-(U1-SW)") (class "Default")
      (node (ref "L1") (pin "1") (pinfunction "1_1") (pintype "passive"))
      (node (ref "U1") (pin "3") (pinfunction "SW_3") (pintype "output"))
    )
    (net (code "89") (name "VBUS_P1") (class "Default")
      (node (ref "C18") (pin "1") (pinfunction "1_1") (pintype "passive"))
      (node (ref "P4") (pin "1") (pinfunction "+5V_1") (pintype "power_in"))
      (node (ref "R45") (pin "2") (pintype "passive"))
      (node (ref "U5") (pin "3") (pinfunction "VI+_3") (pintype "power_in"))
    )
    (net (code "90") (name "VBUS_P2") (class "Default")
      (node (ref "C11") (pin "1") (pinfunction "1_1") (pintype "passive"))
      (node (ref "P2") (pin "1") (pinfunction "+5V_1") (pintype "power_in"))
      (node (ref "R46") (pin "2") (pintype "passive"))
      (node (ref "U6") (pin "3") (pinfunction "VI+_3") (pintype "power_in"))
    )
    (net (code "91") (name "VDD") (class "Default")
      (node (ref "C19") (pin "2") (pinfunction "2_2") (pintype "passive"))
      (node (ref "C22") (pin "2") (pinfunction "2_2") (pintype "passive"))
      (node (ref "C23") (pin "2") (pinfunction "2_2") (pintype "passive"))
      (node (ref "C6") (pin "2") (pinfunction "2_2") (pintype "passive"))
      (node (ref "C8") (pin "1") (pinfunction "1_1") (pintype "passive"))
      (node (ref "D4") (pin "2") (pinfunction "K_2") (pintype "passive"))
      (node (ref "P13") (pin "7") (pinfunction "7_7") (pintype "passive"))
      (node (ref "P13") (pin "8") (pinfunction "8_8") (pintype "passive"))
      (node (ref "R1") (pin "1") (pintype "passive"))
      (node (ref "R4") (pin "1") (pintype "passive"))
      (node (ref "R6") (pin "2") (pinfunction "2_2") (pintype "passive"))
      (node (ref "U2") (pin "18") (pinfunction "VDD_18") (pintype "power_in"))
      (node (ref "U2") (pin "35") (pinfunction "VDD_35") (pintype "power_in"))
      (node (ref "U2") (pin "51") (pinfunction "VDD_51") (pintype "power_in"))
      (node (ref "U2") (pin "68") (pinfunction "VDD_68") (pintype "power_in"))
    )
    (net (code "92") (name "unconnected-(P10-Pad7)") (class "Default")
      (node (ref "P10") (pin "7") (pintype "passive"))
    )
    (net (code "93") (name "unconnected-(S1-NO-Pad3)") (class "Default")
      (node (ref "S1") (pin "3") (pinfunction "NO_3") (pintype "passive"))
    )
    (net (code "94") (name "unconnected-(U1-NC.-Pad1)") (class "Default")
      (node (ref "U1") (pin "1") (pinfunction "NC._1") (pintype "passive"))
    )
  )
)
